# 2014_CARTE_PUISSANCE.net
KiCad netlist of a schematic drawn in Altium Designer
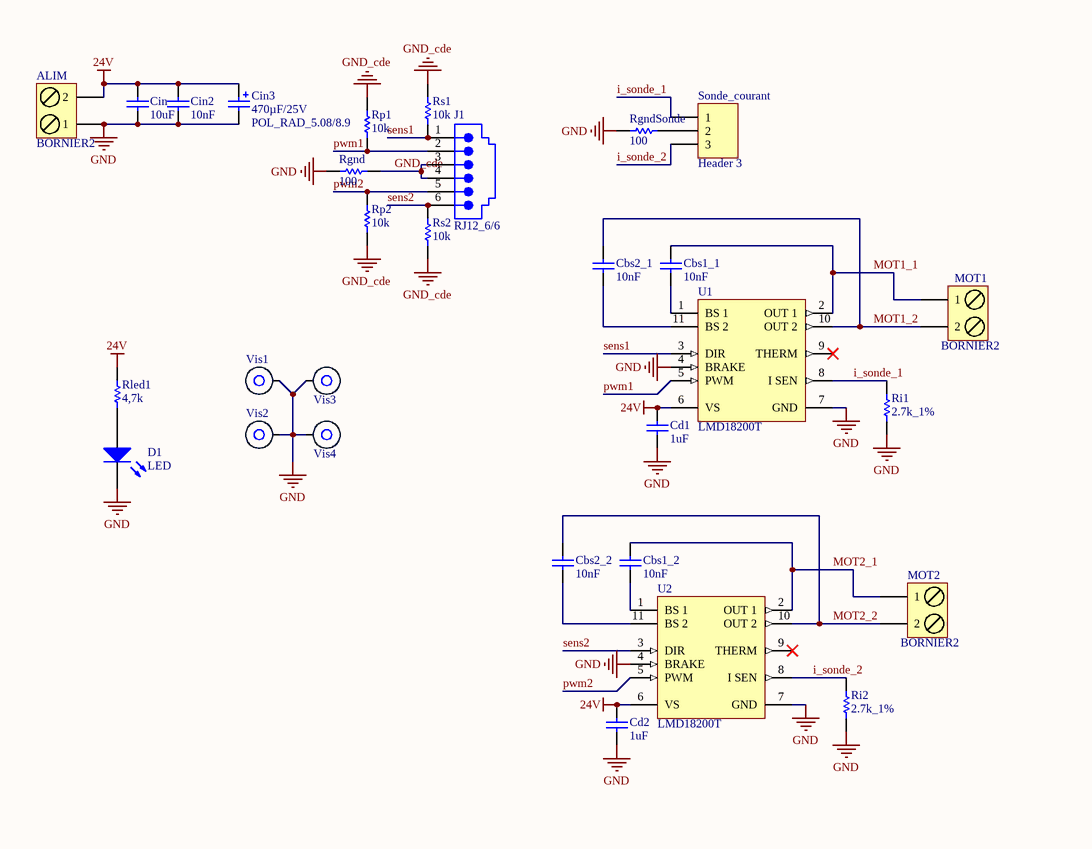
[diagram p0: 2014_CARTE_PUISSANCE.SchDoc, left]
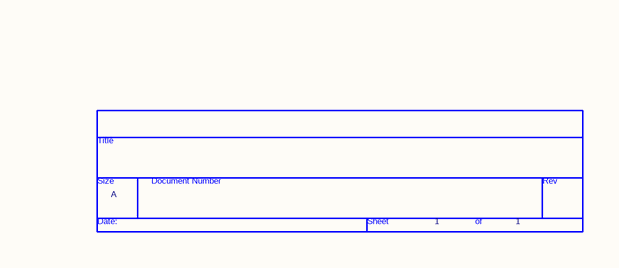
[diagram p1: 2014_CARTE_PUISSANCE.SchDoc, right]

(export (version "E")
  (design (tool "Eeschema 10.0.6"))
  (components
    (comp (ref "*")
      (value "TitleBlock0")
      (fields (field (name "PAGE COUNT") "1") (field (name "PAGE NUMBER") "1") (field (name "PAGE SIZE") "A"))
      (libsource (lib "*") (part "TitleBlock0"))
    )
    (comp (ref "ALIM")
      (value "BORNIER2")
      (footprint "BORNIER2")
      (description "Terminal blocks, 2 pins, pitch=5mm")
      (libsource (lib "Robot2010") (part "BORNIER2"))
    )
    (comp (ref "Cbs1_1")
      (value "10nF")
      (footprint "C0805_N")
      (description "Capacitor")
      (fields (field (name "PUBLISHER") "Altium Limited"))
      (libsource (lib "DG_Condensateur") (part "Capacitor"))
    )
    (comp (ref "Cbs1_2")
      (value "10nF")
      (footprint "C0805_N")
      (description "Capacitor")
      (fields (field (name "PUBLISHER") "Altium Limited"))
      (libsource (lib "DG_Condensateur") (part "Capacitor"))
    )
    (comp (ref "Cbs2_1")
      (value "10nF")
      (footprint "C0805_N")
      (description "Capacitor")
      (fields (field (name "PUBLISHER") "Altium Limited"))
      (libsource (lib "DG_Condensateur") (part "Capacitor"))
    )
    (comp (ref "Cbs2_2")
      (value "10nF")
      (footprint "C0805_N")
      (description "Capacitor")
      (fields (field (name "PUBLISHER") "Altium Limited"))
      (libsource (lib "DG_Condensateur") (part "Capacitor"))
    )
    (comp (ref "Cd1")
      (value "1uF")
      (footprint "C1206_N")
      (description "Capacitor")
      (fields (field (name "PUBLISHER") "Altium Limited"))
      (libsource (lib "DG_Condensateur") (part "Capacitor"))
    )
    (comp (ref "Cd2")
      (value "1uF")
      (footprint "C1206_N")
      (description "Capacitor")
      (fields (field (name "PUBLISHER") "Altium Limited"))
      (libsource (lib "DG_Condensateur") (part "Capacitor"))
    )
    (comp (ref "Cin")
      (value "10uF")
      (footprint "C1206_N")
      (description "Capacitor")
      (fields (field (name "PUBLISHER") "Altium Limited"))
      (libsource (lib "DG_Condensateur") (part "Capacitor"))
    )
    (comp (ref "Cin2")
      (value "10nF")
      (footprint "C0805_N")
      (description "Capacitor")
      (fields (field (name "PUBLISHER") "Altium Limited"))
      (libsource (lib "DG_Condensateur") (part "Capacitor"))
    )
    (comp (ref "Cin3")
      (value "470µF/25V")
      (footprint "CONDENSATEUR_POLARISE_ELECTROLYTIQUE_RADIAL_5.08/8.9")
      (description "CONDENSATEUR POLARISE ELECTROLYTIQUE RADIAL 5.08/8.9")
      (fields
        (field (name "TYPE") "POL_RAD_5.08/8.9")
        (field (name "Comment") "CONDENSATEUR_POL_ELECTROLY_RAD_5.08/8.9")
      )
      (libsource (lib "composants passifs") (part "CONDENSATEUR_POL_ELECTROLY_RAD_5.08/8.9"))
    )
    (comp (ref "D1")
      (value "LED")
      (footprint "LED_3mm")
      (description "Typical LED")
      (fields (field (name "PUBLISHER") "Altium Limited"))
      (libsource (lib "DG_LED") (part "LED"))
    )
    (comp (ref "J1")
      (value "RJ12_6/6")
      (footprint "RJ12_6/6")
      (description "EMBASE RJ12_6/6 COUDEE")
      (fields (field (name "TYPE") "RJ12_6/6"))
      (libsource (lib "connecteurs") (part "RJ12_6/6"))
    )
    (comp (ref "MOT1")
      (value "BORNIER2")
      (footprint "BORNIER_2V_5.08MM")
      (description "Terminal blocks, 2 pins, pitch=5mm")
      (libsource (lib "Connecteur") (part "BORNIER2"))
    )
    (comp (ref "MOT2")
      (value "BORNIER2")
      (footprint "BORNIER_2V_5.08MM")
      (description "Terminal blocks, 2 pins, pitch=5mm")
      (libsource (lib "Connecteur") (part "BORNIER2"))
    )
    (comp (ref "Rgnd")
      (value "100")
      (footprint "R1206_N")
      (description "Resistor")
      (fields (field (name "PUBLISHER") "Altium Limited"))
      (libsource (lib "DG_Resistance") (part "Resistor"))
    )
    (comp (ref "RgndSonde")
      (value "100")
      (footprint "R1206_N")
      (description "Resistor")
      (fields (field (name "PUBLISHER") "Altium Limited"))
      (libsource (lib "DG_Resistance") (part "Resistor"))
    )
    (comp (ref "Ri1")
      (value "2.7k_1%")
      (footprint "R1206_N")
      (description "Resistor")
      (fields (field (name "PUBLISHER") "Altium Limited"))
      (libsource (lib "DG_Resistance") (part "Resistor"))
    )
    (comp (ref "Ri2")
      (value "2.7k_1%")
      (footprint "R1206_N")
      (description "Resistor")
      (fields (field (name "PUBLISHER") "Altium Limited"))
      (libsource (lib "DG_Resistance") (part "Resistor"))
    )
    (comp (ref "Rled1")
      (value "4,7k")
      (footprint "R1206_N")
      (description "Resistor")
      (fields (field (name "PUBLISHER") "Altium Limited"))
      (libsource (lib "DG_Resistance") (part "Resistor"))
    )
    (comp (ref "Rp1")
      (value "10k")
      (footprint "R1206_N")
      (description "Resistor")
      (fields (field (name "PUBLISHER") "Altium Limited"))
      (libsource (lib "DG_Resistance") (part "Resistor"))
    )
    (comp (ref "Rp2")
      (value "10k")
      (footprint "R1206_N")
      (description "Resistor")
      (fields (field (name "PUBLISHER") "Altium Limited"))
      (libsource (lib "DG_Resistance") (part "Resistor"))
    )
    (comp (ref "Rs1")
      (value "10k")
      (footprint "R1206_N")
      (description "Resistor")
      (fields (field (name "PUBLISHER") "Altium Limited"))
      (libsource (lib "DG_Resistance") (part "Resistor"))
    )
    (comp (ref "Rs2")
      (value "10k")
      (footprint "R1206_N")
      (description "Resistor")
      (fields (field (name "PUBLISHER") "Altium Limited"))
      (libsource (lib "DG_Resistance") (part "Resistor"))
    )
    (comp (ref "Sonde_courant")
      (value "Header 3")
      (footprint "HDR1X3")
      (description "Header, 3-Pin")
      (fields (field (name "PUBLISHER") "Altium Limited"))
      (libsource (lib "DG_Connecteur") (part "Header 3"))
    )
    (comp (ref "U1")
      (value "LMD18200T")
      (footprint "TA11B")
      (description "3A, 55V H-Bridge")
      (fields
        (field (name "MANUFACTURER") "National Semiconductor")
        (field (name "DIGIKEYPARTNUMBER") "LMD18200T-ND")
        (field (name "PUBLISHER") "Altium Limited")
      )
      (libsource (lib "NSC MiscPower") (part "LMD18200T"))
    )
    (comp (ref "U2")
      (value "LMD18200T")
      (footprint "TA11B")
      (description "3A, 55V H-Bridge")
      (fields
        (field (name "MANUFACTURER") "National Semiconductor")
        (field (name "DIGIKEYPARTNUMBER") "LMD18200T-ND")
        (field (name "PUBLISHER") "Altium Limited")
      )
      (libsource (lib "NSC MiscPower") (part "LMD18200T"))
    )
    (comp (ref "Vis1")
      (value "Entretoise WURTH CMS")
      (footprint "ENTRETOISE_CMS")
      (description "Entretoise Wurth")
      (fields (field (name "PUBLISHER") "Damien Guitton"))
      (libsource (lib "_ROBOT") (part "Entretoise WURTH CMS"))
    )
    (comp (ref "Vis2")
      (value "Entretoise WURTH CMS")
      (footprint "ENTRETOISE_CMS")
      (description "Entretoise Wurth")
      (fields (field (name "PUBLISHER") "Damien Guitton"))
      (libsource (lib "_ROBOT") (part "Entretoise WURTH CMS"))
    )
    (comp (ref "Vis3")
      (value "Entretoise WURTH CMS")
      (footprint "ENTRETOISE_CMS")
      (description "Entretoise Wurth")
      (fields (field (name "PUBLISHER") "Damien Guitton"))
      (libsource (lib "_ROBOT") (part "Entretoise WURTH CMS"))
    )
    (comp (ref "Vis4")
      (value "Entretoise WURTH CMS")
      (footprint "ENTRETOISE_CMS")
      (description "Entretoise Wurth")
      (fields (field (name "PUBLISHER") "Damien Guitton"))
      (libsource (lib "_ROBOT") (part "Entretoise WURTH CMS"))
    )
  )
  (nets
    (net (code "1") (name "/MOT1_1") (class "Default")
      (node (ref "Cbs1_1") (pin "2") (pinfunction "2_2") (pintype "passive"))
      (node (ref "MOT1") (pin "1") (pinfunction "1_1") (pintype "passive"))
      (node (ref "U1") (pin "2") (pinfunction "OUT_1_2") (pintype "output"))
    )
    (net (code "2") (name "/MOT1_2") (class "Default")
      (node (ref "Cbs2_1") (pin "2") (pinfunction "2_2") (pintype "passive"))
      (node (ref "MOT1") (pin "2") (pinfunction "2_2") (pintype "passive"))
      (node (ref "U1") (pin "10") (pinfunction "OUT_2_10") (pintype "output"))
    )
    (net (code "3") (name "/MOT2_1") (class "Default")
      (node (ref "Cbs1_2") (pin "2") (pinfunction "2_2") (pintype "passive"))
      (node (ref "MOT2") (pin "1") (pinfunction "1_1") (pintype "passive"))
      (node (ref "U2") (pin "2") (pinfunction "OUT_1_2") (pintype "output"))
    )
    (net (code "4") (name "/MOT2_2") (class "Default")
      (node (ref "Cbs2_2") (pin "2") (pinfunction "2_2") (pintype "passive"))
      (node (ref "MOT2") (pin "2") (pinfunction "2_2") (pintype "passive"))
      (node (ref "U2") (pin "10") (pinfunction "OUT_2_10") (pintype "output"))
    )
    (net (code "5") (name "/i_sonde_1") (class "Default")
      (node (ref "Ri1") (pin "1") (pinfunction "1_1") (pintype "passive"))
      (node (ref "Sonde_courant") (pin "1") (pinfunction "1_1") (pintype "passive"))
      (node (ref "U1") (pin "8") (pinfunction "I_SEN_8") (pintype "output"))
    )
    (net (code "6") (name "/i_sonde_2") (class "Default")
      (node (ref "Ri2") (pin "1") (pinfunction "1_1") (pintype "passive"))
      (node (ref "Sonde_courant") (pin "3") (pinfunction "3_3") (pintype "passive"))
      (node (ref "U2") (pin "8") (pinfunction "I_SEN_8") (pintype "output"))
    )
    (net (code "7") (name "/pwm1") (class "Default")
      (node (ref "J1") (pin "2") (pinfunction "2_2") (pintype "passive"))
      (node (ref "Rp1") (pin "1") (pinfunction "1_1") (pintype "passive"))
      (node (ref "U1") (pin "5") (pinfunction "PWM_5") (pintype "input"))
    )
    (net (code "8") (name "/pwm2") (class "Default")
      (node (ref "J1") (pin "5") (pinfunction "5_5") (pintype "passive"))
      (node (ref "Rp2") (pin "2") (pinfunction "2_2") (pintype "passive"))
      (node (ref "U2") (pin "5") (pinfunction "PWM_5") (pintype "input"))
    )
    (net (code "9") (name "/sens1") (class "Default")
      (node (ref "J1") (pin "1") (pinfunction "1_1") (pintype "passive"))
      (node (ref "Rs1") (pin "1") (pinfunction "1_1") (pintype "passive"))
      (node (ref "U1") (pin "3") (pinfunction "DIR_3") (pintype "input"))
    )
    (net (code "10") (name "/sens2") (class "Default")
      (node (ref "J1") (pin "6") (pinfunction "6_6") (pintype "passive"))
      (node (ref "Rs2") (pin "2") (pinfunction "2_2") (pintype "passive"))
      (node (ref "U2") (pin "3") (pinfunction "DIR_3") (pintype "input"))
    )
    (net (code "11") (name "24V") (class "Default")
      (node (ref "ALIM") (pin "2") (pinfunction "2_2") (pintype "passive"))
      (node (ref "Cd1") (pin "1") (pinfunction "1_1") (pintype "passive"))
      (node (ref "Cd2") (pin "1") (pinfunction "1_1") (pintype "passive"))
      (node (ref "Cin") (pin "2") (pinfunction "2_2") (pintype "passive"))
      (node (ref "Cin2") (pin "2") (pinfunction "2_2") (pintype "passive"))
      (node (ref "Cin3") (pin "1") (pinfunction "1_1") (pintype "passive"))
      (node (ref "Rled1") (pin "2") (pinfunction "2_2") (pintype "passive"))
      (node (ref "U1") (pin "6") (pinfunction "VS_6") (pintype "power_in"))
      (node (ref "U2") (pin "6") (pinfunction "VS_6") (pintype "power_in"))
    )
    (net (code "12") (name "GND") (class "Default")
      (node (ref "ALIM") (pin "1") (pinfunction "1_1") (pintype "passive"))
      (node (ref "Cd1") (pin "2") (pinfunction "2_2") (pintype "passive"))
      (node (ref "Cd2") (pin "2") (pinfunction "2_2") (pintype "passive"))
      (node (ref "Cin") (pin "1") (pinfunction "1_1") (pintype "passive"))
      (node (ref "Cin2") (pin "1") (pinfunction "1_1") (pintype "passive"))
      (node (ref "Cin3") (pin "2") (pinfunction "2_2") (pintype "passive"))
      (node (ref "D1") (pin "2") (pinfunction "2_2") (pintype "passive"))
      (node (ref "Rgnd") (pin "2") (pinfunction "2_2") (pintype "passive"))
      (node (ref "RgndSonde") (pin "2") (pinfunction "2_2") (pintype "passive"))
      (node (ref "Ri1") (pin "2") (pinfunction "2_2") (pintype "passive"))
      (node (ref "Ri2") (pin "2") (pinfunction "2_2") (pintype "passive"))
      (node (ref "U1") (pin "4") (pinfunction "BRAKE_4") (pintype "input"))
      (node (ref "U1") (pin "7") (pinfunction "GND_7") (pintype "power_in"))
      (node (ref "U2") (pin "4") (pinfunction "BRAKE_4") (pintype "input"))
      (node (ref "U2") (pin "7") (pinfunction "GND_7") (pintype "power_in"))
      (node (ref "Vis1") (pin "1") (pinfunction "1_1") (pintype "passive"))
      (node (ref "Vis2") (pin "1") (pinfunction "1_1") (pintype "passive"))
      (node (ref "Vis3") (pin "1") (pinfunction "1_1") (pintype "passive"))
      (node (ref "Vis4") (pin "1") (pinfunction "1_1") (pintype "passive"))
    )
    (net (code "13") (name "GND_cde") (class "Default")
      (node (ref "J1") (pin "3") (pinfunction "3_3") (pintype "passive"))
      (node (ref "J1") (pin "4") (pinfunction "4_4") (pintype "passive"))
      (node (ref "Rgnd") (pin "1") (pinfunction "1_1") (pintype "passive"))
      (node (ref "Rp1") (pin "2") (pinfunction "2_2") (pintype "passive"))
      (node (ref "Rp2") (pin "1") (pinfunction "1_1") (pintype "passive"))
      (node (ref "Rs1") (pin "2") (pinfunction "2_2") (pintype "passive"))
      (node (ref "Rs2") (pin "1") (pinfunction "1_1") (pintype "passive"))
    )
    (net (code "14") (name "Net-(D1-Pad1)") (class "Default")
      (node (ref "D1") (pin "1") (pinfunction "1_1") (pintype "passive"))
      (node (ref "Rled1") (pin "1") (pinfunction "1_1") (pintype "passive"))
    )
    (net (code "15") (name "Net-(RgndSonde-Pad1)") (class "Default")
      (node (ref "RgndSonde") (pin "1") (pinfunction "1_1") (pintype "passive"))
      (node (ref "Sonde_courant") (pin "2") (pinfunction "2_2") (pintype "passive"))
    )
    (net (code "16") (name "Net-(U1-BS_1)") (class "Default")
      (node (ref "Cbs1_1") (pin "1") (pinfunction "1_1") (pintype "passive"))
      (node (ref "U1") (pin "1") (pinfunction "BS_1_1") (pintype "passive"))
    )
    (net (code "17") (name "Net-(U1-BS_2)") (class "Default")
      (node (ref "Cbs2_1") (pin "1") (pinfunction "1_1") (pintype "passive"))
      (node (ref "U1") (pin "11") (pinfunction "BS_2_11") (pintype "passive"))
    )
    (net (code "18") (name "Net-(U2-BS_1)") (class "Default")
      (node (ref "Cbs1_2") (pin "1") (pinfunction "1_1") (pintype "passive"))
      (node (ref "U2") (pin "1") (pinfunction "BS_1_1") (pintype "passive"))
    )
    (net (code "19") (name "Net-(U2-BS_2)") (class "Default")
      (node (ref "Cbs2_2") (pin "1") (pinfunction "1_1") (pintype "passive"))
      (node (ref "U2") (pin "11") (pinfunction "BS_2_11") (pintype "passive"))
    )
    (net (code "20") (name "unconnected-(U1-THERM-Pad9)") (class "Default")
      (node (ref "U1") (pin "9") (pinfunction "THERM_9") (pintype "output+no_connect"))
    )
    (net (code "21") (name "unconnected-(U2-THERM-Pad9)") (class "Default")
      (node (ref "U2") (pin "9") (pinfunction "THERM_9") (pintype "output+no_connect"))
    )
  )
)
